# Piggyback_PhotonenDetector.net
KiCad netlist of a schematic drawn in EAGLE
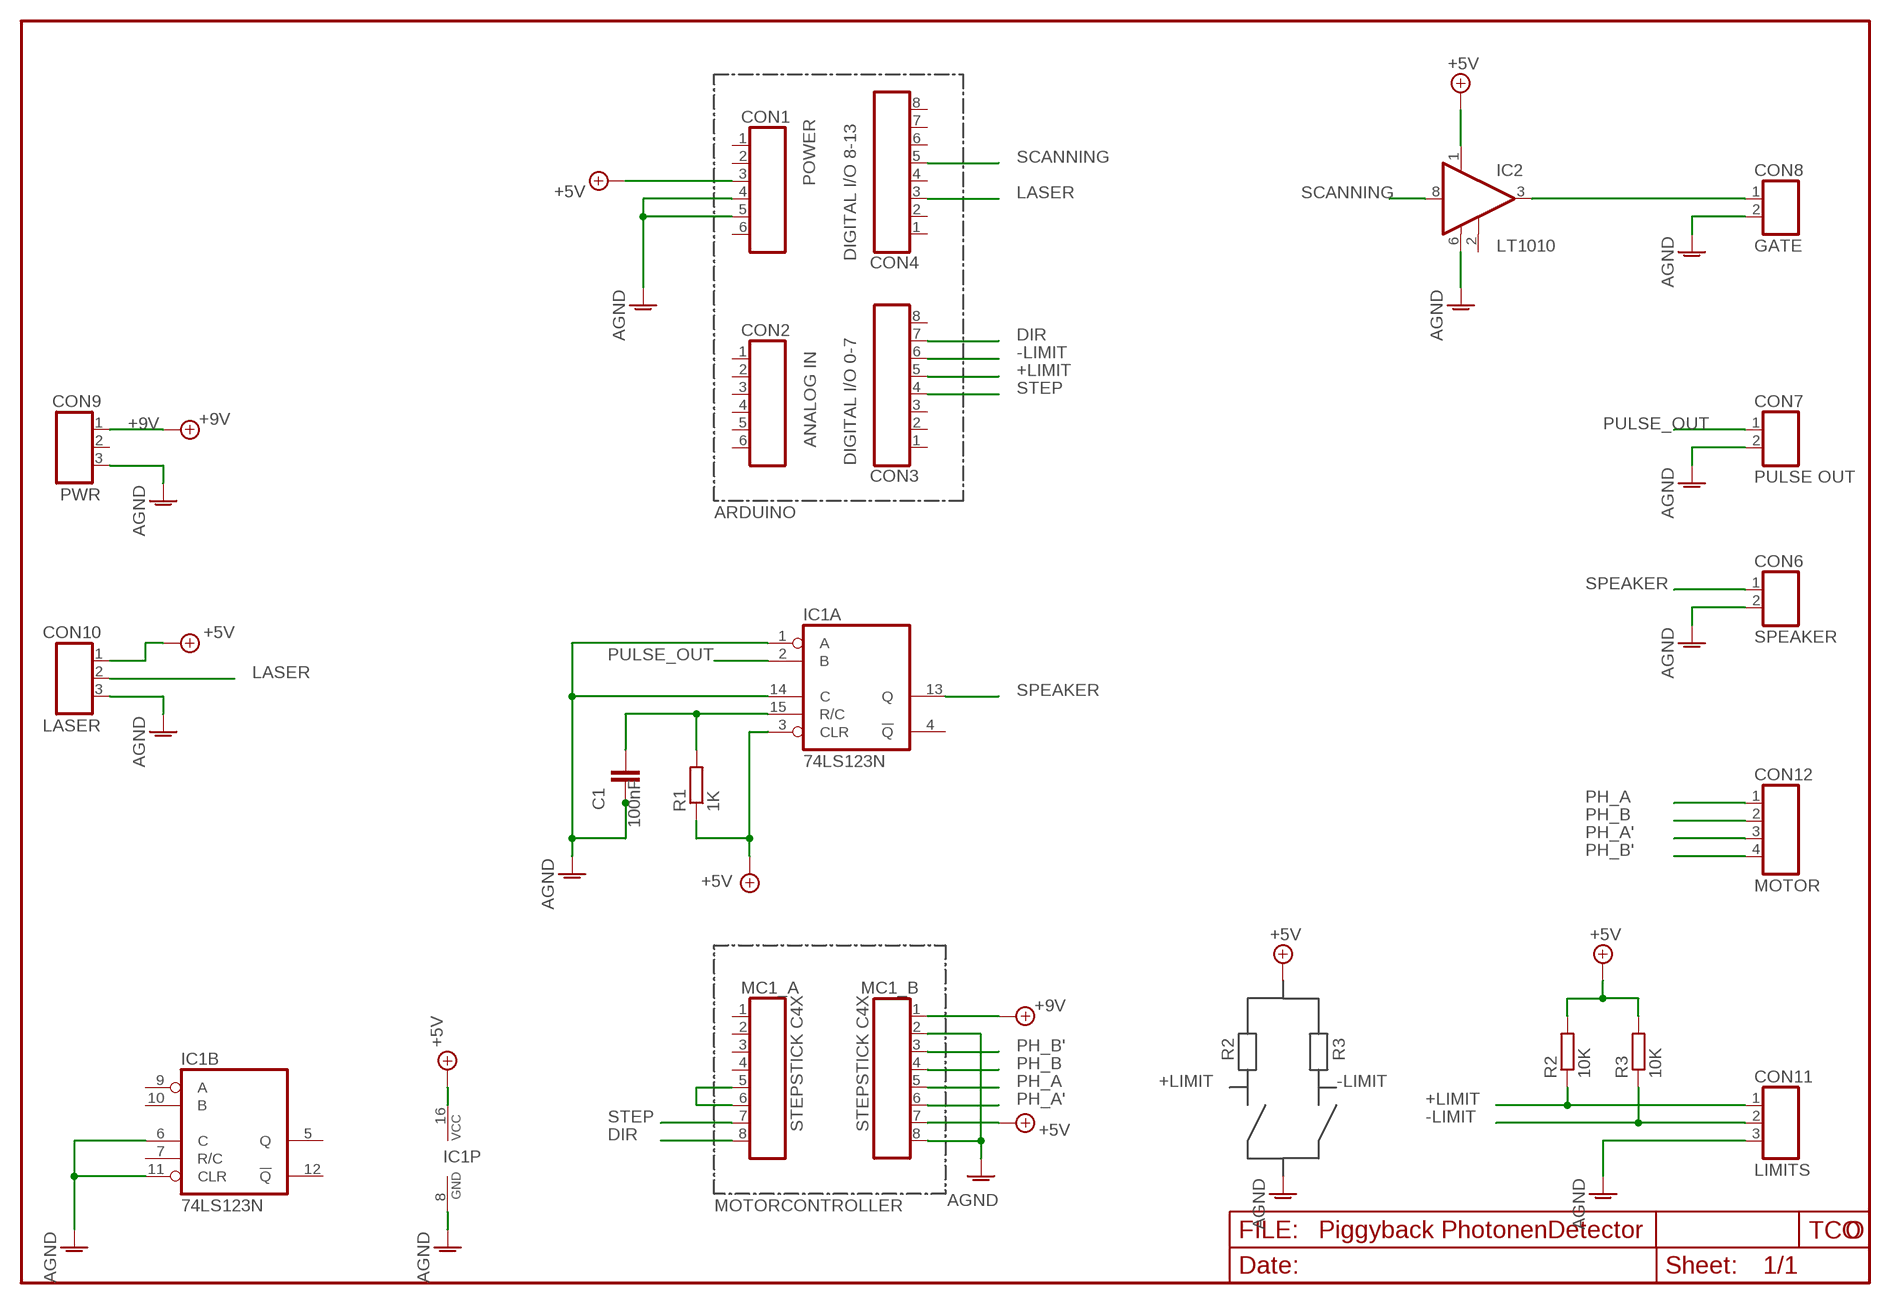
[diagram p0: schematic, sheet 1]

(export (version "E")
  (design (tool "Eeschema 10.0.6"))
  (components
    (comp (ref "C1")
      (value "100nF")
      (footprint "eagle-import:C025_050-025X075")
      (libsource (lib "eagle-import") (part "C-EU025_050-025X075"))
    )
    (comp (ref "CON1")
      (value "POWER")
      (footprint "eagle-import:HDR-06-2.54")
      (libsource (lib "eagle-import") (part "HD6-HDR-S"))
    )
    (comp (ref "CON2")
      (value "ANALOG IN")
      (footprint "eagle-import:HDR-06-2.54")
      (libsource (lib "eagle-import") (part "HD6-HDR-S"))
    )
    (comp (ref "CON3")
      (value "DIGITAL I/O 0-7")
      (footprint "eagle-import:HDR-08-2.54")
      (libsource (lib "eagle-import") (part "HD8-HDR-S"))
    )
    (comp (ref "CON4")
      (value "DIGITAL I/O 8-13")
      (footprint "eagle-import:HDR-08-2.54")
      (libsource (lib "eagle-import") (part "HD8-HDR-S"))
    )
    (comp (ref "CON6")
      (value "SPEAKER")
      (footprint "eagle-import:HDR-02-2.54")
      (libsource (lib "eagle-import") (part "HD2-HDR-S"))
    )
    (comp (ref "CON7")
      (value "PULSE OUT")
      (footprint "eagle-import:HDR-02-2.54")
      (libsource (lib "eagle-import") (part "HD2-HDR-S"))
    )
    (comp (ref "CON8")
      (value "GATE")
      (footprint "eagle-import:HDR-02-2.54")
      (libsource (lib "eagle-import") (part "HD2-HDR-S"))
    )
    (comp (ref "CON9")
      (value "PWR")
      (footprint "eagle-import:HDR-03-2.54")
      (libsource (lib "eagle-import") (part "HD3-HDR-S"))
    )
    (comp (ref "CON10")
      (value "LASER")
      (footprint "eagle-import:HDR-03-2.54")
      (libsource (lib "eagle-import") (part "HD3-HDR-S"))
    )
    (comp (ref "CON11")
      (value "LIMITS")
      (footprint "eagle-import:HDR-03-2.54")
      (libsource (lib "eagle-import") (part "HD3-HDR-S"))
    )
    (comp (ref "CON12")
      (value "MOTOR")
      (footprint "eagle-import:HDR-04-2.54")
      (libsource (lib "eagle-import") (part "HD4-HDR-S"))
    )
    (comp (ref "IC1")
      (value "74LS123N")
      (footprint "eagle-import:DIL16")
      (libsource (lib "eagle-import") (part "74123NLS"))
    )
    (comp (ref "IC2")
      (value "LT1010")
      (footprint "eagle-import:DIL08")
      (libsource (lib "eagle-import") (part "LT1010N8"))
    )
    (comp (ref "MC1_A")
      (value "STEPSTICK C4X")
      (footprint "eagle-import:HDR-08-2.54")
      (libsource (lib "eagle-import") (part "HD8-HDR-S"))
    )
    (comp (ref "MC1_B")
      (value "STEPSTICK C4X")
      (footprint "eagle-import:HDR-08-2.54")
      (libsource (lib "eagle-import") (part "HD8-HDR-S"))
    )
    (comp (ref "R1")
      (value "1K")
      (footprint "eagle-import:0207_10")
      (libsource (lib "eagle-import") (part "R-EU_0207/10"))
    )
    (comp (ref "R2")
      (value "10K")
      (footprint "eagle-import:0207_10")
      (libsource (lib "eagle-import") (part "R-EU_0207/10"))
    )
    (comp (ref "R3")
      (value "10K")
      (footprint "eagle-import:0207_10")
      (libsource (lib "eagle-import") (part "R-EU_0207/10"))
    )
  )
  (nets
    (net (code "1") (name "+5V") (class "Default")
      (node (ref "CON1") (pin "3") (pinfunction "3_3") (pintype "passive"))
      (node (ref "CON10") (pin "1") (pinfunction "1_1") (pintype "passive"))
      (node (ref "IC1") (pin "16") (pinfunction "VCC_16") (pintype "power_in"))
      (node (ref "IC1") (pin "3") (pinfunction "CLR_3") (pintype "input"))
      (node (ref "IC2") (pin "1") (pinfunction "V+_1") (pintype "power_in"))
      (node (ref "MC1_B") (pin "7") (pinfunction "7_7") (pintype "passive"))
      (node (ref "R1") (pin "1") (pinfunction "1_1") (pintype "passive"))
      (node (ref "R2") (pin "2") (pinfunction "2_2") (pintype "passive"))
      (node (ref "R3") (pin "2") (pinfunction "2_2") (pintype "passive"))
    )
    (net (code "2") (name "+9V") (class "Default")
      (node (ref "CON9") (pin "1") (pinfunction "1_1") (pintype "passive"))
      (node (ref "MC1_B") (pin "1") (pinfunction "1_1") (pintype "passive"))
    )
    (net (code "3") (name "/+LIMIT") (class "Default")
      (node (ref "CON11") (pin "1") (pinfunction "1_1") (pintype "passive"))
      (node (ref "CON3") (pin "5") (pinfunction "5_5") (pintype "passive"))
      (node (ref "R2") (pin "1") (pinfunction "1_1") (pintype "passive"))
    )
    (net (code "4") (name "/-LIMIT") (class "Default")
      (node (ref "CON11") (pin "2") (pinfunction "2_2") (pintype "passive"))
      (node (ref "CON3") (pin "6") (pinfunction "6_6") (pintype "passive"))
      (node (ref "R3") (pin "1") (pinfunction "1_1") (pintype "passive"))
    )
    (net (code "5") (name "/DIR") (class "Default")
      (node (ref "CON3") (pin "7") (pinfunction "7_7") (pintype "passive"))
      (node (ref "MC1_A") (pin "8") (pinfunction "8_8") (pintype "passive"))
    )
    (net (code "6") (name "/LASER") (class "Default")
      (node (ref "CON10") (pin "2") (pinfunction "2_2") (pintype "passive"))
      (node (ref "CON4") (pin "3") (pinfunction "3_3") (pintype "passive"))
    )
    (net (code "7") (name "/PH_A") (class "Default")
      (node (ref "CON12") (pin "1") (pinfunction "1_1") (pintype "passive"))
      (node (ref "MC1_B") (pin "5") (pinfunction "5_5") (pintype "passive"))
    )
    (net (code "8") (name "/PH_A'") (class "Default")
      (node (ref "CON12") (pin "3") (pinfunction "3_3") (pintype "passive"))
      (node (ref "MC1_B") (pin "6") (pinfunction "6_6") (pintype "passive"))
    )
    (net (code "9") (name "/PH_B") (class "Default")
      (node (ref "CON12") (pin "2") (pinfunction "2_2") (pintype "passive"))
      (node (ref "MC1_B") (pin "4") (pinfunction "4_4") (pintype "passive"))
    )
    (net (code "10") (name "/PH_B'") (class "Default")
      (node (ref "CON12") (pin "4") (pinfunction "4_4") (pintype "passive"))
      (node (ref "MC1_B") (pin "3") (pinfunction "3_3") (pintype "passive"))
    )
    (net (code "11") (name "/PULSE_OUT") (class "Default")
      (node (ref "CON7") (pin "1") (pinfunction "1_1") (pintype "passive"))
      (node (ref "IC1") (pin "2") (pinfunction "B_2") (pintype "input"))
    )
    (net (code "12") (name "/SCANNING") (class "Default")
      (node (ref "CON4") (pin "5") (pinfunction "5_5") (pintype "passive"))
      (node (ref "IC2") (pin "8") (pinfunction "+IN_8") (pintype "input"))
    )
    (net (code "13") (name "/SPEAKER") (class "Default")
      (node (ref "CON6") (pin "1") (pinfunction "1_1") (pintype "passive"))
      (node (ref "IC1") (pin "13") (pinfunction "Q_13") (pintype "output"))
    )
    (net (code "14") (name "/STEP") (class "Default")
      (node (ref "CON3") (pin "4") (pinfunction "4_4") (pintype "passive"))
      (node (ref "MC1_A") (pin "7") (pinfunction "7_7") (pintype "passive"))
    )
    (net (code "15") (name "AGND") (class "Default")
      (node (ref "C1") (pin "2") (pinfunction "2_2") (pintype "passive"))
      (node (ref "C1") (pin "3") (pinfunction "P$1_3") (pintype "passive"))
      (node (ref "CON1") (pin "4") (pinfunction "4_4") (pintype "passive"))
      (node (ref "CON1") (pin "5") (pinfunction "5_5") (pintype "passive"))
      (node (ref "CON10") (pin "3") (pinfunction "3_3") (pintype "passive"))
      (node (ref "CON11") (pin "3") (pinfunction "3_3") (pintype "passive"))
      (node (ref "CON6") (pin "2") (pinfunction "2_2") (pintype "passive"))
      (node (ref "CON7") (pin "2") (pinfunction "2_2") (pintype "passive"))
      (node (ref "CON8") (pin "2") (pinfunction "2_2") (pintype "passive"))
      (node (ref "CON9") (pin "3") (pinfunction "3_3") (pintype "passive"))
      (node (ref "IC1") (pin "1") (pinfunction "A_1") (pintype "input"))
      (node (ref "IC1") (pin "11") (pinfunction "CLR_11") (pintype "input"))
      (node (ref "IC1") (pin "14") (pinfunction "C_14") (pintype "input"))
      (node (ref "IC1") (pin "6") (pinfunction "C_6") (pintype "input"))
      (node (ref "IC1") (pin "8") (pinfunction "GND_8") (pintype "power_in"))
      (node (ref "IC2") (pin "6") (pinfunction "V-_6") (pintype "power_in"))
      (node (ref "MC1_B") (pin "2") (pinfunction "2_2") (pintype "passive"))
      (node (ref "MC1_B") (pin "8") (pinfunction "8_8") (pintype "passive"))
    )
    (net (code "16") (name "Net-(IC1A-R{slash}C)") (class "Default")
      (node (ref "C1") (pin "1") (pinfunction "1_1") (pintype "passive"))
      (node (ref "IC1") (pin "15") (pinfunction "R/C_15") (pintype "input"))
      (node (ref "R1") (pin "2") (pinfunction "2_2") (pintype "passive"))
    )
    (net (code "17") (name "Net-(IC2-OUT)") (class "Default")
      (node (ref "CON8") (pin "1") (pinfunction "1_1") (pintype "passive"))
      (node (ref "IC2") (pin "3") (pinfunction "OUT_3") (pintype "output"))
    )
    (net (code "18") (name "Net-(MC1_A-Pad5)") (class "Default")
      (node (ref "MC1_A") (pin "5") (pinfunction "5_5") (pintype "passive"))
      (node (ref "MC1_A") (pin "6") (pinfunction "6_6") (pintype "passive"))
    )
    (net (code "19") (name "unconnected-(CON1-Pad1)") (class "Default")
      (node (ref "CON1") (pin "1") (pinfunction "1_1") (pintype "passive"))
    )
    (net (code "20") (name "unconnected-(CON1-Pad2)") (class "Default")
      (node (ref "CON1") (pin "2") (pinfunction "2_2") (pintype "passive"))
    )
    (net (code "21") (name "unconnected-(CON1-Pad6)") (class "Default")
      (node (ref "CON1") (pin "6") (pinfunction "6_6") (pintype "passive"))
    )
    (net (code "22") (name "unconnected-(CON2-Pad1)") (class "Default")
      (node (ref "CON2") (pin "1") (pinfunction "1_1") (pintype "passive"))
    )
    (net (code "23") (name "unconnected-(CON2-Pad2)") (class "Default")
      (node (ref "CON2") (pin "2") (pinfunction "2_2") (pintype "passive"))
    )
    (net (code "24") (name "unconnected-(CON2-Pad3)") (class "Default")
      (node (ref "CON2") (pin "3") (pinfunction "3_3") (pintype "passive"))
    )
    (net (code "25") (name "unconnected-(CON2-Pad4)") (class "Default")
      (node (ref "CON2") (pin "4") (pinfunction "4_4") (pintype "passive"))
    )
    (net (code "26") (name "unconnected-(CON2-Pad5)") (class "Default")
      (node (ref "CON2") (pin "5") (pinfunction "5_5") (pintype "passive"))
    )
    (net (code "27") (name "unconnected-(CON2-Pad6)") (class "Default")
      (node (ref "CON2") (pin "6") (pinfunction "6_6") (pintype "passive"))
    )
    (net (code "28") (name "unconnected-(CON3-Pad1)") (class "Default")
      (node (ref "CON3") (pin "1") (pinfunction "1_1") (pintype "passive"))
    )
    (net (code "29") (name "unconnected-(CON3-Pad2)") (class "Default")
      (node (ref "CON3") (pin "2") (pinfunction "2_2") (pintype "passive"))
    )
    (net (code "30") (name "unconnected-(CON3-Pad3)") (class "Default")
      (node (ref "CON3") (pin "3") (pinfunction "3_3") (pintype "passive"))
    )
    (net (code "31") (name "unconnected-(CON3-Pad8)") (class "Default")
      (node (ref "CON3") (pin "8") (pinfunction "8_8") (pintype "passive"))
    )
    (net (code "32") (name "unconnected-(CON4-Pad1)") (class "Default")
      (node (ref "CON4") (pin "1") (pinfunction "1_1") (pintype "passive"))
    )
    (net (code "33") (name "unconnected-(CON4-Pad2)") (class "Default")
      (node (ref "CON4") (pin "2") (pinfunction "2_2") (pintype "passive"))
    )
    (net (code "34") (name "unconnected-(CON4-Pad4)") (class "Default")
      (node (ref "CON4") (pin "4") (pinfunction "4_4") (pintype "passive"))
    )
    (net (code "35") (name "unconnected-(CON4-Pad6)") (class "Default")
      (node (ref "CON4") (pin "6") (pinfunction "6_6") (pintype "passive"))
    )
    (net (code "36") (name "unconnected-(CON4-Pad7)") (class "Default")
      (node (ref "CON4") (pin "7") (pinfunction "7_7") (pintype "passive"))
    )
    (net (code "37") (name "unconnected-(CON4-Pad8)") (class "Default")
      (node (ref "CON4") (pin "8") (pinfunction "8_8") (pintype "passive"))
    )
    (net (code "38") (name "unconnected-(CON9-Pad2)") (class "Default")
      (node (ref "CON9") (pin "2") (pinfunction "2_2") (pintype "passive"))
    )
    (net (code "39") (name "unconnected-(IC1A-~{Q}-Pad4)") (class "Default")
      (node (ref "IC1") (pin "4") (pinfunction "~{Q}_4") (pintype "output"))
    )
    (net (code "40") (name "unconnected-(IC1B-A-Pad9)") (class "Default")
      (node (ref "IC1") (pin "9") (pinfunction "A_9") (pintype "input"))
    )
    (net (code "41") (name "unconnected-(IC1B-B-Pad10)") (class "Default")
      (node (ref "IC1") (pin "10") (pinfunction "B_10") (pintype "input"))
    )
    (net (code "42") (name "unconnected-(IC1B-Q-Pad5)") (class "Default")
      (node (ref "IC1") (pin "5") (pinfunction "Q_5") (pintype "output"))
    )
    (net (code "43") (name "unconnected-(IC1B-R{slash}C-Pad7)") (class "Default")
      (node (ref "IC1") (pin "7") (pinfunction "R/C_7") (pintype "input"))
    )
    (net (code "44") (name "unconnected-(IC1B-~{Q}-Pad12)") (class "Default")
      (node (ref "IC1") (pin "12") (pinfunction "~{Q}_12") (pintype "output"))
    )
    (net (code "45") (name "unconnected-(IC2-BIAS-Pad2)") (class "Default")
      (node (ref "IC2") (pin "2") (pinfunction "BIAS_2") (pintype "passive"))
    )
    (net (code "46") (name "unconnected-(MC1_A-Pad1)") (class "Default")
      (node (ref "MC1_A") (pin "1") (pinfunction "1_1") (pintype "passive"))
    )
    (net (code "47") (name "unconnected-(MC1_A-Pad2)") (class "Default")
      (node (ref "MC1_A") (pin "2") (pinfunction "2_2") (pintype "passive"))
    )
    (net (code "48") (name "unconnected-(MC1_A-Pad3)") (class "Default")
      (node (ref "MC1_A") (pin "3") (pinfunction "3_3") (pintype "passive"))
    )
    (net (code "49") (name "unconnected-(MC1_A-Pad4)") (class "Default")
      (node (ref "MC1_A") (pin "4") (pinfunction "4_4") (pintype "passive"))
    )
  )
)
